# socket_power_supply.net
KiCad netlist of a schematic drawn in Altium Designer
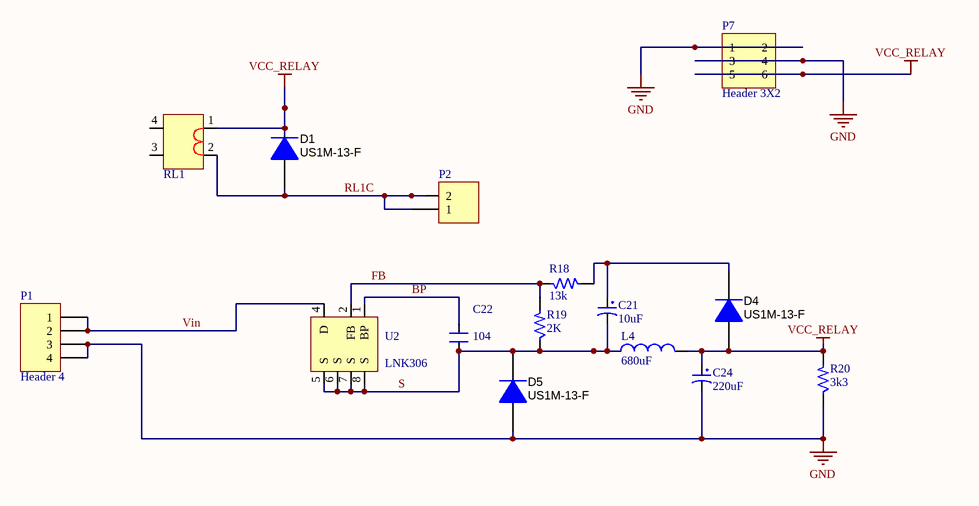
[diagram p0: socket_power_supply.SchDoc]

(export (version "E")
  (design (tool "Eeschema 10.0.6"))
  (components
    (comp (ref "C21")
      (value "10uF")
      (footprint "TU_NHOM_10uF_MH")
      (description "TU_NHOM_10uF_25V_MH")
      (libsource (lib "MH_DA_THU_VIEN_16122016") (part "TU_NHOM_10uF_25V_MH"))
    )
    (comp (ref "C22")
      (value "104")
      (footprint "0805_HV")
      (description "Cap SMD")
      (libsource (lib "hatcatbietbay") (part "CM"))
    )
    (comp (ref "C24")
      (value "220uF")
      (footprint "TU_NHOM_2.5_MH")
      (description "TU_NHOM_220uF_25V_MH")
      (libsource (lib "MH_DA_THU_VIEN_16122016") (part "TU_NHOM_220uF_25V_MH"))
    )
    (comp (ref "D1")
      (value "US1M-13-F")
      (footprint "PcbLib1:SMB")
      (description "Diode, Ultrafast, 600V, 1A, SMB")
      (fields
        (field (name "PARTNUMBER") "US1M-13-F")
        (field (name "MANUFACTURER") "Diodes Inc.")
        (field (name "PUBLISHER") "Texas Instruments")
      )
      (libsource (lib "Diode") (part "MURS160-13-F"))
    )
    (comp (ref "D4")
      (value "US1M-13-F")
      (footprint "PcbLib1:SMB")
      (description "Diode, Ultrafast, 600V, 1A, SMB")
      (fields
        (field (name "PARTNUMBER") "US1M-13-F")
        (field (name "MANUFACTURER") "Diodes Inc.")
        (field (name "PUBLISHER") "Texas Instruments")
      )
      (libsource (lib "Diode") (part "MURS160-13-F"))
    )
    (comp (ref "D5")
      (value "US1M-13-F")
      (footprint "PcbLib1:SMB")
      (description "Diode, Ultrafast, 600V, 1A, SMB")
      (fields
        (field (name "PARTNUMBER") "US1M-13-F")
        (field (name "MANUFACTURER") "Diodes Inc.")
        (field (name "PUBLISHER") "Texas Instruments")
      )
      (libsource (lib "Diode") (part "MURS160-13-F"))
    )
    (comp (ref "L4")
      (value "680uF")
      (footprint "Inductor 4.5x5")
      (libsource (lib "MH_DA_THU_VIEN_16122016") (part "Inductor 4.5x5_MH"))
    )
    (comp (ref "P1")
      (value "Header 4")
      (footprint "HDR1X4")
      (description "Header, 4-Pin")
      (fields (field (name "PUBLISHER") "Altium Limited"))
      (libsource (lib "Miscellaneous Connectors") (part "Header 4"))
    )
    (comp (ref "P2")
      (value "Header 2")
      (footprint "HDR1X2")
      (description "Header, 2-Pin")
      (fields (field (name "PUBLISHER") "Altium Limited"))
      (libsource (lib "Miscellaneous Connectors") (part "Header 2"))
    )
    (comp (ref "P7")
      (value "Header 3X2")
      (footprint "HDR2X3")
      (description "Header, 3-Pin, Dual row")
      (fields (field (name "PUBLISHER") "Altium Limited"))
      (libsource (lib "Miscellaneous Connectors") (part "Header 3X2"))
    )
    (comp (ref "R18")
      (value "13k")
      (footprint "0805_HV")
      (description "Resistor 1/4W")
      (libsource (lib "hatcatbietbay") (part "R"))
    )
    (comp (ref "R19")
      (value "2K")
      (footprint "0805_HV")
      (description "Resistor 1/4W")
      (libsource (lib "hatcatbietbay") (part "R"))
    )
    (comp (ref "R20")
      (value "3k3")
      (footprint "0805_HV")
      (description "Resistor 1/4W")
      (libsource (lib "hatcatbietbay") (part "R"))
    )
    (comp (ref "RL1")
      (value "Component_1")
      (footprint "RELAY25AOMRON")
      (libsource (lib "Zettler") (part "Component_1"))
    )
    (comp (ref "U2") (value "LNK306") (footprint "SOP 7") (libsource (lib "LNK304") (part "Component_1")))
  )
  (nets
    (net (code "1") (name "/BP") (class "Default")
      (node (ref "C22") (pin "2") (pinfunction "2_2") (pintype "passive"))
      (node (ref "U2") (pin "1") (pinfunction "BP_1") (pintype "passive"))
    )
    (net (code "2") (name "/FB") (class "Default")
      (node (ref "R18") (pin "1") (pinfunction "1_1") (pintype "passive"))
      (node (ref "R19") (pin "2") (pinfunction "2_2") (pintype "passive"))
      (node (ref "U2") (pin "2") (pinfunction "FB_2") (pintype "passive"))
    )
    (net (code "3") (name "/RL1C") (class "Default")
      (node (ref "D1") (pin "2") (pinfunction "A_2") (pintype "passive"))
      (node (ref "P2") (pin "1") (pinfunction "1_1") (pintype "passive"))
      (node (ref "P2") (pin "2") (pinfunction "2_2") (pintype "passive"))
      (node (ref "RL1") (pin "2") (pintype "passive"))
    )
    (net (code "4") (name "/S") (class "Default")
      (node (ref "C21") (pin "2") (pinfunction "2_2") (pintype "passive"))
      (node (ref "C22") (pin "1") (pinfunction "1_1") (pintype "passive"))
      (node (ref "D5") (pin "1") (pinfunction "K_1") (pintype "passive"))
      (node (ref "L4") (pin "1") (pinfunction "1_1") (pintype "passive"))
      (node (ref "R19") (pin "1") (pinfunction "1_1") (pintype "passive"))
      (node (ref "U2") (pin "5") (pinfunction "S_5") (pintype "passive"))
      (node (ref "U2") (pin "6") (pinfunction "S_6") (pintype "passive"))
      (node (ref "U2") (pin "7") (pinfunction "S_7") (pintype "passive"))
      (node (ref "U2") (pin "8") (pinfunction "S_8") (pintype "passive"))
    )
    (net (code "5") (name "/Vin") (class "Default")
      (node (ref "P1") (pin "1") (pinfunction "1_1") (pintype "passive"))
      (node (ref "P1") (pin "2") (pinfunction "2_2") (pintype "passive"))
      (node (ref "U2") (pin "4") (pinfunction "D_4") (pintype "passive"))
    )
    (net (code "6") (name "GND") (class "Default")
      (node (ref "C24") (pin "2") (pinfunction "2_2") (pintype "passive"))
      (node (ref "D5") (pin "2") (pinfunction "A_2") (pintype "passive"))
      (node (ref "P1") (pin "3") (pinfunction "3_3") (pintype "passive"))
      (node (ref "P1") (pin "4") (pinfunction "4_4") (pintype "passive"))
      (node (ref "P7") (pin "1") (pinfunction "1_1") (pintype "passive"))
      (node (ref "P7") (pin "2") (pinfunction "2_2") (pintype "passive"))
      (node (ref "P7") (pin "3") (pinfunction "3_3") (pintype "passive"))
      (node (ref "P7") (pin "4") (pinfunction "4_4") (pintype "passive"))
      (node (ref "R20") (pin "1") (pinfunction "1_1") (pintype "passive"))
    )
    (net (code "7") (name "Net-(D4-K)") (class "Default")
      (node (ref "C21") (pin "1") (pinfunction "1_1") (pintype "passive"))
      (node (ref "D4") (pin "1") (pinfunction "K_1") (pintype "passive"))
      (node (ref "R18") (pin "2") (pinfunction "2_2") (pintype "passive"))
    )
    (net (code "8") (name "VCC_RELAY") (class "Default")
      (node (ref "C24") (pin "1") (pinfunction "1_1") (pintype "passive"))
      (node (ref "D1") (pin "1") (pinfunction "K_1") (pintype "passive"))
      (node (ref "D4") (pin "2") (pinfunction "A_2") (pintype "passive"))
      (node (ref "L4") (pin "2") (pinfunction "2_2") (pintype "passive"))
      (node (ref "P7") (pin "5") (pinfunction "5_5") (pintype "passive"))
      (node (ref "P7") (pin "6") (pinfunction "6_6") (pintype "passive"))
      (node (ref "R20") (pin "2") (pinfunction "2_2") (pintype "passive"))
      (node (ref "RL1") (pin "1") (pintype "passive"))
    )
    (net (code "9") (name "unconnected-(RL1-Pad3)") (class "Default")
      (node (ref "RL1") (pin "3") (pintype "passive"))
    )
    (net (code "10") (name "unconnected-(RL1-Pad4)") (class "Default")
      (node (ref "RL1") (pin "4") (pintype "passive"))
    )
  )
)
